# shield.net
KiCad netlist of a schematic drawn in EAGLE
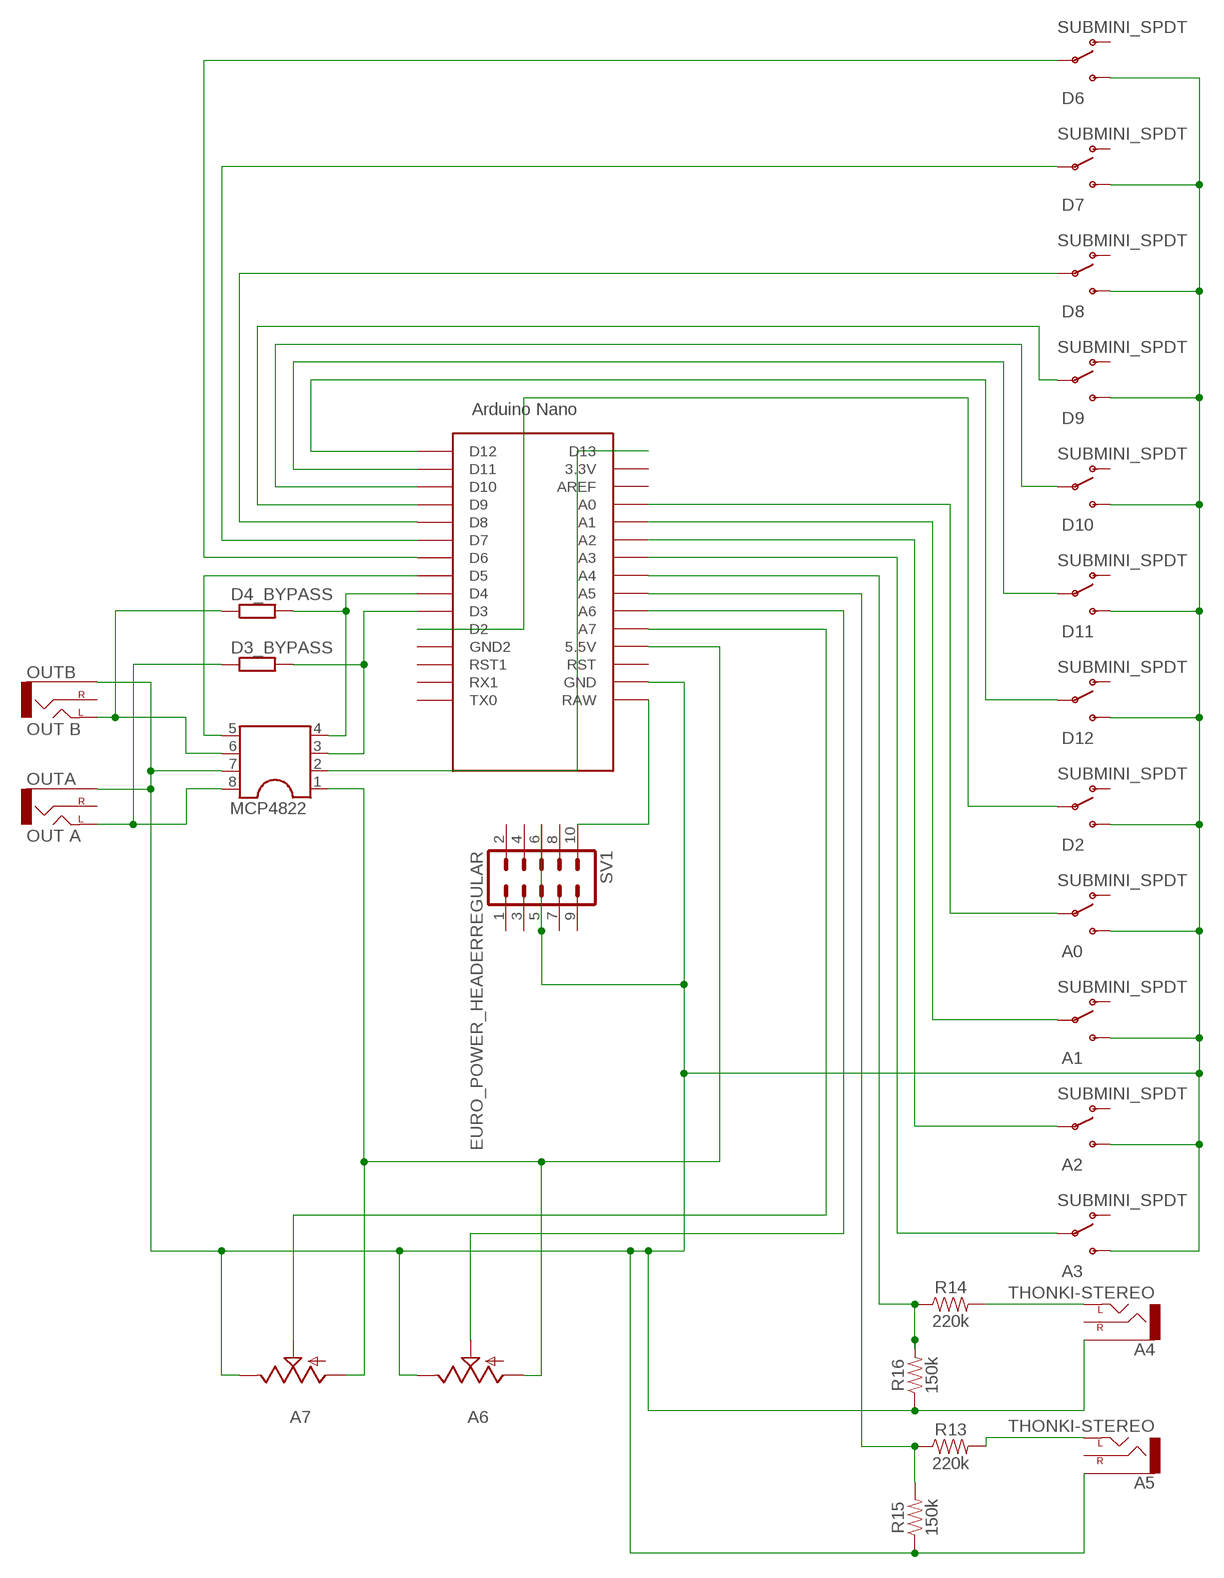
[diagram p0: schematic, sheet 1]

(export (version "E")
  (design (tool "Eeschema 10.0.6"))
  (components
    (comp (ref "A0")
      (value "SUBMINI_SPDT")
      (footprint "eagle-import:SUBMINI_TOGGLE")
      (libsource (lib "eagle-import") (part "SUBMINI_SPDT"))
    )
    (comp (ref "A1")
      (value "SUBMINI_SPDT")
      (footprint "eagle-import:SUBMINI_TOGGLE")
      (libsource (lib "eagle-import") (part "SUBMINI_SPDT"))
    )
    (comp (ref "A2")
      (value "SUBMINI_SPDT")
      (footprint "eagle-import:SUBMINI_TOGGLE")
      (libsource (lib "eagle-import") (part "SUBMINI_SPDT"))
    )
    (comp (ref "A3")
      (value "SUBMINI_SPDT")
      (footprint "eagle-import:SUBMINI_TOGGLE")
      (libsource (lib "eagle-import") (part "SUBMINI_SPDT"))
    )
    (comp (ref "A4")
      (value "THONKI-STEREO")
      (footprint "eagle-import:WQP-PJ366ST_JACK")
      (libsource (lib "eagle-import") (part "THONKI-STEREO"))
    )
    (comp (ref "A5")
      (value "THONKI-STEREO")
      (footprint "eagle-import:WQP-PJ366ST_JACK")
      (libsource (lib "eagle-import") (part "THONKI-STEREO"))
    )
    (comp (ref "A6")
      (value "9MM_SNAP-IN_POT_")
      (footprint "eagle-import:9MM_SNAP-IN_POT")
      (libsource (lib "eagle-import") (part "9MM_SNAP-IN_POT_"))
    )
    (comp (ref "A7")
      (value "9MM_SNAP-IN_POT_")
      (footprint "eagle-import:9MM_SNAP-IN_POT")
      (libsource (lib "eagle-import") (part "9MM_SNAP-IN_POT_"))
    )
    (comp (ref "D2")
      (value "SUBMINI_SPDT")
      (footprint "eagle-import:SUBMINI_TOGGLE")
      (libsource (lib "eagle-import") (part "SUBMINI_SPDT"))
    )
    (comp (ref "D3_BYPASS")
      (value "RESISTOR7MM")
      (footprint "eagle-import:7MM_RESISTOR")
      (libsource (lib "eagle-import") (part "RESISTOR7MM"))
    )
    (comp (ref "D4_BYPASS")
      (value "RESISTOR7MM")
      (footprint "eagle-import:7MM_RESISTOR")
      (libsource (lib "eagle-import") (part "RESISTOR7MM"))
    )
    (comp (ref "D6")
      (value "SUBMINI_SPDT")
      (footprint "eagle-import:SUBMINI_TOGGLE")
      (libsource (lib "eagle-import") (part "SUBMINI_SPDT"))
    )
    (comp (ref "D7")
      (value "SUBMINI_SPDT")
      (footprint "eagle-import:SUBMINI_TOGGLE")
      (libsource (lib "eagle-import") (part "SUBMINI_SPDT"))
    )
    (comp (ref "D8")
      (value "SUBMINI_SPDT")
      (footprint "eagle-import:SUBMINI_TOGGLE")
      (libsource (lib "eagle-import") (part "SUBMINI_SPDT"))
    )
    (comp (ref "D9")
      (value "SUBMINI_SPDT")
      (footprint "eagle-import:SUBMINI_TOGGLE")
      (libsource (lib "eagle-import") (part "SUBMINI_SPDT"))
    )
    (comp (ref "D10")
      (value "SUBMINI_SPDT")
      (footprint "eagle-import:SUBMINI_TOGGLE")
      (libsource (lib "eagle-import") (part "SUBMINI_SPDT"))
    )
    (comp (ref "D11")
      (value "SUBMINI_SPDT")
      (footprint "eagle-import:SUBMINI_TOGGLE")
      (libsource (lib "eagle-import") (part "SUBMINI_SPDT"))
    )
    (comp (ref "D12")
      (value "SUBMINI_SPDT")
      (footprint "eagle-import:SUBMINI_TOGGLE")
      (libsource (lib "eagle-import") (part "SUBMINI_SPDT"))
    )
    (comp (ref "MCP4822")
      (value "DIL8")
      (footprint "eagle-import:DIL08")
      (libsource (lib "eagle-import") (part "DIL8"))
    )
    (comp (ref "OUTA")
      (value "OUT A")
      (footprint "eagle-import:WQP-PJ366ST_JACK")
      (libsource (lib "eagle-import") (part "THONKI-STEREO"))
    )
    (comp (ref "OUTB")
      (value "OUT B")
      (footprint "eagle-import:WQP-PJ366ST_JACK")
      (libsource (lib "eagle-import") (part "THONKI-STEREO"))
    )
    (comp (ref "R13")
      (value "220k")
      (footprint "eagle-import:AXIAL-0.3")
      (libsource (lib "eagle-import") (part "10KOHM-HORIZ-1/4W-5%"))
    )
    (comp (ref "R14")
      (value "220k")
      (footprint "eagle-import:AXIAL-0.3")
      (libsource (lib "eagle-import") (part "10KOHM-HORIZ-1/4W-5%"))
    )
    (comp (ref "R15")
      (value "150k")
      (footprint "eagle-import:AXIAL-0.3")
      (libsource (lib "eagle-import") (part "10KOHM-HORIZ-1/4W-5%"))
    )
    (comp (ref "R16")
      (value "150k")
      (footprint "eagle-import:AXIAL-0.3")
      (libsource (lib "eagle-import") (part "10KOHM-HORIZ-1/4W-5%"))
    )
    (comp (ref "SV1")
      (value "EURO_POWER_HEADERREGULAR")
      (footprint "eagle-import:EURO_POWER_HEADER")
      (libsource (lib "eagle-import") (part "EURO_POWER_HEADERREGULAR"))
    )
    (comp (ref "U$1")
      (value "NANO")
      (footprint "eagle-import:NANO")
      (libsource (lib "eagle-import") (part "NANO"))
    )
  )
  (nets
    (net (code "1") (name "Net-(A0-COMMON)") (class "Default")
      (node (ref "A0") (pin "COM") (pinfunction "COMMON_COM") (pintype "passive"))
      (node (ref "U$1") (pin "A0") (pinfunction "A0_A0") (pintype "bidirectional"))
    )
    (net (code "2") (name "Net-(A0-S)") (class "Default")
      (node (ref "A0") (pin "3") (pinfunction "S_3") (pintype "passive"))
      (node (ref "A1") (pin "3") (pinfunction "S_3") (pintype "passive"))
      (node (ref "A2") (pin "3") (pinfunction "S_3") (pintype "passive"))
      (node (ref "A3") (pin "3") (pinfunction "S_3") (pintype "passive"))
      (node (ref "A4") (pin "P$3_SLEEVE") (pinfunction "SLEEVE_P$3_SLEEVE") (pintype "bidirectional"))
      (node (ref "A5") (pin "P$3_SLEEVE") (pinfunction "SLEEVE_P$3_SLEEVE") (pintype "bidirectional"))
      (node (ref "A6") (pin "3") (pinfunction "E_3") (pintype "passive"))
      (node (ref "A7") (pin "3") (pinfunction "E_3") (pintype "passive"))
      (node (ref "D10") (pin "3") (pinfunction "S_3") (pintype "passive"))
      (node (ref "D11") (pin "3") (pinfunction "S_3") (pintype "passive"))
      (node (ref "D12") (pin "3") (pinfunction "S_3") (pintype "passive"))
      (node (ref "D2") (pin "3") (pinfunction "S_3") (pintype "passive"))
      (node (ref "D6") (pin "3") (pinfunction "S_3") (pintype "passive"))
      (node (ref "D7") (pin "3") (pinfunction "S_3") (pintype "passive"))
      (node (ref "D8") (pin "3") (pinfunction "S_3") (pintype "passive"))
      (node (ref "D9") (pin "3") (pinfunction "S_3") (pintype "passive"))
      (node (ref "MCP4822") (pin "7") (pinfunction "7_7") (pintype "passive"))
      (node (ref "OUTA") (pin "P$3_SLEEVE") (pinfunction "SLEEVE_P$3_SLEEVE") (pintype "bidirectional"))
      (node (ref "OUTB") (pin "P$3_SLEEVE") (pinfunction "SLEEVE_P$3_SLEEVE") (pintype "bidirectional"))
      (node (ref "R15") (pin "P$1") (pinfunction "1_P$1") (pintype "passive"))
      (node (ref "R16") (pin "P$1") (pinfunction "1_P$1") (pintype "passive"))
      (node (ref "SV1") (pin "5") (pinfunction "5_5") (pintype "passive"))
      (node (ref "SV1") (pin "6") (pinfunction "6_6") (pintype "passive"))
      (node (ref "U$1") (pin "GND") (pinfunction "GND_GND") (pintype "bidirectional"))
    )
    (net (code "3") (name "Net-(A1-COMMON)") (class "Default")
      (node (ref "A1") (pin "COM") (pinfunction "COMMON_COM") (pintype "passive"))
      (node (ref "U$1") (pin "A1") (pinfunction "A1_A1") (pintype "bidirectional"))
    )
    (net (code "4") (name "Net-(A2-COMMON)") (class "Default")
      (node (ref "A2") (pin "COM") (pinfunction "COMMON_COM") (pintype "passive"))
      (node (ref "U$1") (pin "A2") (pinfunction "A2_A2") (pintype "bidirectional"))
    )
    (net (code "5") (name "Net-(A3-COMMON)") (class "Default")
      (node (ref "A3") (pin "COM") (pinfunction "COMMON_COM") (pintype "passive"))
      (node (ref "U$1") (pin "A3") (pinfunction "A3_A3") (pintype "bidirectional"))
    )
    (net (code "6") (name "Net-(A4-LEFT)") (class "Default")
      (node (ref "A4") (pin "P$1_TIP") (pinfunction "LEFT_P$1_TIP") (pintype "bidirectional"))
      (node (ref "R14") (pin "P$2") (pinfunction "2_P$2") (pintype "passive"))
    )
    (net (code "7") (name "Net-(A5-LEFT)") (class "Default")
      (node (ref "A5") (pin "P$1_TIP") (pinfunction "LEFT_P$1_TIP") (pintype "bidirectional"))
      (node (ref "R13") (pin "P$2") (pinfunction "2_P$2") (pintype "passive"))
    )
    (net (code "8") (name "Net-(A6-A)") (class "Default")
      (node (ref "A6") (pin "1") (pinfunction "A_1") (pintype "passive"))
      (node (ref "A7") (pin "1") (pinfunction "A_1") (pintype "passive"))
      (node (ref "MCP4822") (pin "1") (pinfunction "1_1") (pintype "passive"))
      (node (ref "U$1") (pin "5V") (pinfunction "5.5V_5V") (pintype "bidirectional"))
    )
    (net (code "9") (name "Net-(A6-S)") (class "Default")
      (node (ref "A6") (pin "2") (pinfunction "S_2") (pintype "passive"))
      (node (ref "U$1") (pin "A6") (pinfunction "A6_A6") (pintype "bidirectional"))
    )
    (net (code "10") (name "Net-(A7-S)") (class "Default")
      (node (ref "A7") (pin "2") (pinfunction "S_2") (pintype "passive"))
      (node (ref "U$1") (pin "A7") (pinfunction "A7_A7") (pintype "bidirectional"))
    )
    (net (code "11") (name "Net-(D2-COMMON)") (class "Default")
      (node (ref "D2") (pin "COM") (pinfunction "COMMON_COM") (pintype "passive"))
      (node (ref "U$1") (pin "D2") (pinfunction "D2_D2") (pintype "bidirectional"))
    )
    (net (code "12") (name "Net-(D3_BYPASS-Pad2)") (class "Default")
      (node (ref "D3_BYPASS") (pin "2") (pinfunction "2_2") (pintype "passive"))
      (node (ref "MCP4822") (pin "3") (pinfunction "3_3") (pintype "passive"))
      (node (ref "U$1") (pin "D3") (pinfunction "D3_D3") (pintype "bidirectional"))
    )
    (net (code "13") (name "Net-(D4_BYPASS-Pad2)") (class "Default")
      (node (ref "D4_BYPASS") (pin "2") (pinfunction "2_2") (pintype "passive"))
      (node (ref "MCP4822") (pin "4") (pinfunction "4_4") (pintype "passive"))
      (node (ref "U$1") (pin "D4") (pinfunction "D4_D4") (pintype "bidirectional"))
    )
    (net (code "14") (name "Net-(D6-COMMON)") (class "Default")
      (node (ref "D6") (pin "COM") (pinfunction "COMMON_COM") (pintype "passive"))
      (node (ref "U$1") (pin "D6") (pinfunction "D6_D6") (pintype "bidirectional"))
    )
    (net (code "15") (name "Net-(D7-COMMON)") (class "Default")
      (node (ref "D7") (pin "COM") (pinfunction "COMMON_COM") (pintype "passive"))
      (node (ref "U$1") (pin "D7") (pinfunction "D7_D7") (pintype "bidirectional"))
    )
    (net (code "16") (name "Net-(D8-COMMON)") (class "Default")
      (node (ref "D8") (pin "COM") (pinfunction "COMMON_COM") (pintype "passive"))
      (node (ref "U$1") (pin "D8") (pinfunction "D8_D8") (pintype "bidirectional"))
    )
    (net (code "17") (name "Net-(D9-COMMON)") (class "Default")
      (node (ref "D9") (pin "COM") (pinfunction "COMMON_COM") (pintype "passive"))
      (node (ref "U$1") (pin "D9") (pinfunction "D9_D9") (pintype "bidirectional"))
    )
    (net (code "18") (name "Net-(D10-COMMON)") (class "Default")
      (node (ref "D10") (pin "COM") (pinfunction "COMMON_COM") (pintype "passive"))
      (node (ref "U$1") (pin "D10") (pinfunction "D10_D10") (pintype "bidirectional"))
    )
    (net (code "19") (name "Net-(D11-COMMON)") (class "Default")
      (node (ref "D11") (pin "COM") (pinfunction "COMMON_COM") (pintype "passive"))
      (node (ref "U$1") (pin "D11") (pinfunction "D11_D11") (pintype "bidirectional"))
    )
    (net (code "20") (name "Net-(D12-COMMON)") (class "Default")
      (node (ref "D12") (pin "COM") (pinfunction "COMMON_COM") (pintype "passive"))
      (node (ref "U$1") (pin "D12") (pinfunction "D12_D12") (pintype "bidirectional"))
    )
    (net (code "21") (name "Net-(MCP4822-Pad2)") (class "Default")
      (node (ref "MCP4822") (pin "2") (pinfunction "2_2") (pintype "passive"))
      (node (ref "U$1") (pin "D13") (pinfunction "D13_D13") (pintype "bidirectional"))
    )
    (net (code "22") (name "Net-(MCP4822-Pad5)") (class "Default")
      (node (ref "MCP4822") (pin "5") (pinfunction "5_5") (pintype "passive"))
      (node (ref "U$1") (pin "D5") (pinfunction "D5_D5") (pintype "bidirectional"))
    )
    (net (code "23") (name "Net-(OUTA-LEFT)") (class "Default")
      (node (ref "D3_BYPASS") (pin "1") (pinfunction "1_1") (pintype "passive"))
      (node (ref "MCP4822") (pin "8") (pinfunction "8_8") (pintype "passive"))
      (node (ref "OUTA") (pin "P$1_TIP") (pinfunction "LEFT_P$1_TIP") (pintype "bidirectional"))
    )
    (net (code "24") (name "Net-(OUTB-LEFT)") (class "Default")
      (node (ref "D4_BYPASS") (pin "1") (pinfunction "1_1") (pintype "passive"))
      (node (ref "MCP4822") (pin "6") (pinfunction "6_6") (pintype "passive"))
      (node (ref "OUTB") (pin "P$1_TIP") (pinfunction "LEFT_P$1_TIP") (pintype "bidirectional"))
    )
    (net (code "25") (name "Net-(R13-1)") (class "Default")
      (node (ref "R13") (pin "P$1") (pinfunction "1_P$1") (pintype "passive"))
      (node (ref "R15") (pin "P$2") (pinfunction "2_P$2") (pintype "passive"))
      (node (ref "U$1") (pin "A5") (pinfunction "A5_A5") (pintype "bidirectional"))
    )
    (net (code "26") (name "Net-(R14-1)") (class "Default")
      (node (ref "R14") (pin "P$1") (pinfunction "1_P$1") (pintype "passive"))
      (node (ref "R16") (pin "P$2") (pinfunction "2_P$2") (pintype "passive"))
      (node (ref "U$1") (pin "A4") (pinfunction "A4_A4") (pintype "bidirectional"))
    )
    (net (code "27") (name "Net-(SV1-Pad10)") (class "Default")
      (node (ref "SV1") (pin "10") (pinfunction "10_10") (pintype "passive"))
      (node (ref "U$1") (pin "RAW") (pinfunction "RAW_RAW") (pintype "bidirectional"))
    )
    (net (code "28") (name "unconnected-(A0-O-Pad1)") (class "Default")
      (node (ref "A0") (pin "1") (pinfunction "O_1") (pintype "passive"))
    )
    (net (code "29") (name "unconnected-(A1-O-Pad1)") (class "Default")
      (node (ref "A1") (pin "1") (pinfunction "O_1") (pintype "passive"))
    )
    (net (code "30") (name "unconnected-(A2-O-Pad1)") (class "Default")
      (node (ref "A2") (pin "1") (pinfunction "O_1") (pintype "passive"))
    )
    (net (code "31") (name "unconnected-(A3-O-Pad1)") (class "Default")
      (node (ref "A3") (pin "1") (pinfunction "O_1") (pintype "passive"))
    )
    (net (code "32") (name "unconnected-(A4-RIGHT-PadP$2_SWITCH)") (class "Default")
      (node (ref "A4") (pin "P$2_SWITCH") (pinfunction "RIGHT_P$2_SWITCH") (pintype "bidirectional"))
    )
    (net (code "33") (name "unconnected-(A5-RIGHT-PadP$2_SWITCH)") (class "Default")
      (node (ref "A5") (pin "P$2_SWITCH") (pinfunction "RIGHT_P$2_SWITCH") (pintype "bidirectional"))
    )
    (net (code "34") (name "unconnected-(D2-O-Pad1)") (class "Default")
      (node (ref "D2") (pin "1") (pinfunction "O_1") (pintype "passive"))
    )
    (net (code "35") (name "unconnected-(D6-O-Pad1)") (class "Default")
      (node (ref "D6") (pin "1") (pinfunction "O_1") (pintype "passive"))
    )
    (net (code "36") (name "unconnected-(D7-O-Pad1)") (class "Default")
      (node (ref "D7") (pin "1") (pinfunction "O_1") (pintype "passive"))
    )
    (net (code "37") (name "unconnected-(D8-O-Pad1)") (class "Default")
      (node (ref "D8") (pin "1") (pinfunction "O_1") (pintype "passive"))
    )
    (net (code "38") (name "unconnected-(D9-O-Pad1)") (class "Default")
      (node (ref "D9") (pin "1") (pinfunction "O_1") (pintype "passive"))
    )
    (net (code "39") (name "unconnected-(D10-O-Pad1)") (class "Default")
      (node (ref "D10") (pin "1") (pinfunction "O_1") (pintype "passive"))
    )
    (net (code "40") (name "unconnected-(D11-O-Pad1)") (class "Default")
      (node (ref "D11") (pin "1") (pinfunction "O_1") (pintype "passive"))
    )
    (net (code "41") (name "unconnected-(D12-O-Pad1)") (class "Default")
      (node (ref "D12") (pin "1") (pinfunction "O_1") (pintype "passive"))
    )
    (net (code "42") (name "unconnected-(OUTA-RIGHT-PadP$2_SWITCH)") (class "Default")
      (node (ref "OUTA") (pin "P$2_SWITCH") (pinfunction "RIGHT_P$2_SWITCH") (pintype "bidirectional"))
    )
    (net (code "43") (name "unconnected-(OUTB-RIGHT-PadP$2_SWITCH)") (class "Default")
      (node (ref "OUTB") (pin "P$2_SWITCH") (pinfunction "RIGHT_P$2_SWITCH") (pintype "bidirectional"))
    )
    (net (code "44") (name "unconnected-(SV1-Pad1)") (class "Default")
      (node (ref "SV1") (pin "1") (pinfunction "1_1") (pintype "passive"))
    )
    (net (code "45") (name "unconnected-(SV1-Pad2)") (class "Default")
      (node (ref "SV1") (pin "2") (pinfunction "2_2") (pintype "passive"))
    )
    (net (code "46") (name "unconnected-(SV1-Pad3)") (class "Default")
      (node (ref "SV1") (pin "3") (pinfunction "3_3") (pintype "passive"))
    )
    (net (code "47") (name "unconnected-(SV1-Pad4)") (class "Default")
      (node (ref "SV1") (pin "4") (pinfunction "4_4") (pintype "passive"))
    )
    (net (code "48") (name "unconnected-(SV1-Pad7)") (class "Default")
      (node (ref "SV1") (pin "7") (pinfunction "7_7") (pintype "passive"))
    )
    (net (code "49") (name "unconnected-(SV1-Pad8)") (class "Default")
      (node (ref "SV1") (pin "8") (pinfunction "8_8") (pintype "passive"))
    )
    (net (code "50") (name "unconnected-(SV1-Pad9)") (class "Default")
      (node (ref "SV1") (pin "9") (pinfunction "9_9") (pintype "passive"))
    )
    (net (code "51") (name "unconnected-(U$1-GND2-PadGND1)") (class "Default")
      (node (ref "U$1") (pin "GND1") (pinfunction "GND2_GND1") (pintype "bidirectional"))
    )
    (net (code "52") (name "unconnected-(U$1-Pad3.3V)") (class "Default")
      (node (ref "U$1") (pin "3.3V") (pinfunction "3.3V_3.3V") (pintype "bidirectional"))
    )
    (net (code "53") (name "unconnected-(U$1-PadAREF)") (class "Default")
      (node (ref "U$1") (pin "AREF") (pinfunction "AREF_AREF") (pintype "bidirectional"))
    )
    (net (code "54") (name "unconnected-(U$1-PadICSP1)") (class "Default")
      (node (ref "U$1") (pin "ICSP1") (pinfunction "ICSP1_ICSP1") (pintype "bidirectional"))
    )
    (net (code "55") (name "unconnected-(U$1-PadICSP2)") (class "Default")
      (node (ref "U$1") (pin "ICSP2") (pinfunction "ICSP2_ICSP2") (pintype "bidirectional"))
    )
    (net (code "56") (name "unconnected-(U$1-PadICSP3)") (class "Default")
      (node (ref "U$1") (pin "ICSP3") (pinfunction "ICSP3_ICSP3") (pintype "bidirectional"))
    )
    (net (code "57") (name "unconnected-(U$1-PadICSP4)") (class "Default")
      (node (ref "U$1") (pin "ICSP4") (pinfunction "ICSP4_ICSP4") (pintype "bidirectional"))
    )
    (net (code "58") (name "unconnected-(U$1-PadICSP5)") (class "Default")
      (node (ref "U$1") (pin "ICSP5") (pinfunction "ICSP5_ICSP5") (pintype "bidirectional"))
    )
    (net (code "59") (name "unconnected-(U$1-PadICSP6)") (class "Default")
      (node (ref "U$1") (pin "ICSP6") (pinfunction "ICSP6_ICSP6") (pintype "bidirectional"))
    )
    (net (code "60") (name "unconnected-(U$1-PadRST)") (class "Default")
      (node (ref "U$1") (pin "RST") (pinfunction "RST_RST") (pintype "bidirectional"))
    )
    (net (code "61") (name "unconnected-(U$1-PadRST1)") (class "Default")
      (node (ref "U$1") (pin "RST1") (pinfunction "RST1_RST1") (pintype "bidirectional"))
    )
    (net (code "62") (name "unconnected-(U$1-PadRX1)") (class "Default")
      (node (ref "U$1") (pin "RX1") (pinfunction "RX1_RX1") (pintype "bidirectional"))
    )
    (net (code "63") (name "unconnected-(U$1-PadTX0)") (class "Default")
      (node (ref "U$1") (pin "TX0") (pinfunction "TX0_TX0") (pintype "bidirectional"))
    )
  )
)
